# sensorboard.net
KiCad netlist of a schematic drawn in EAGLE
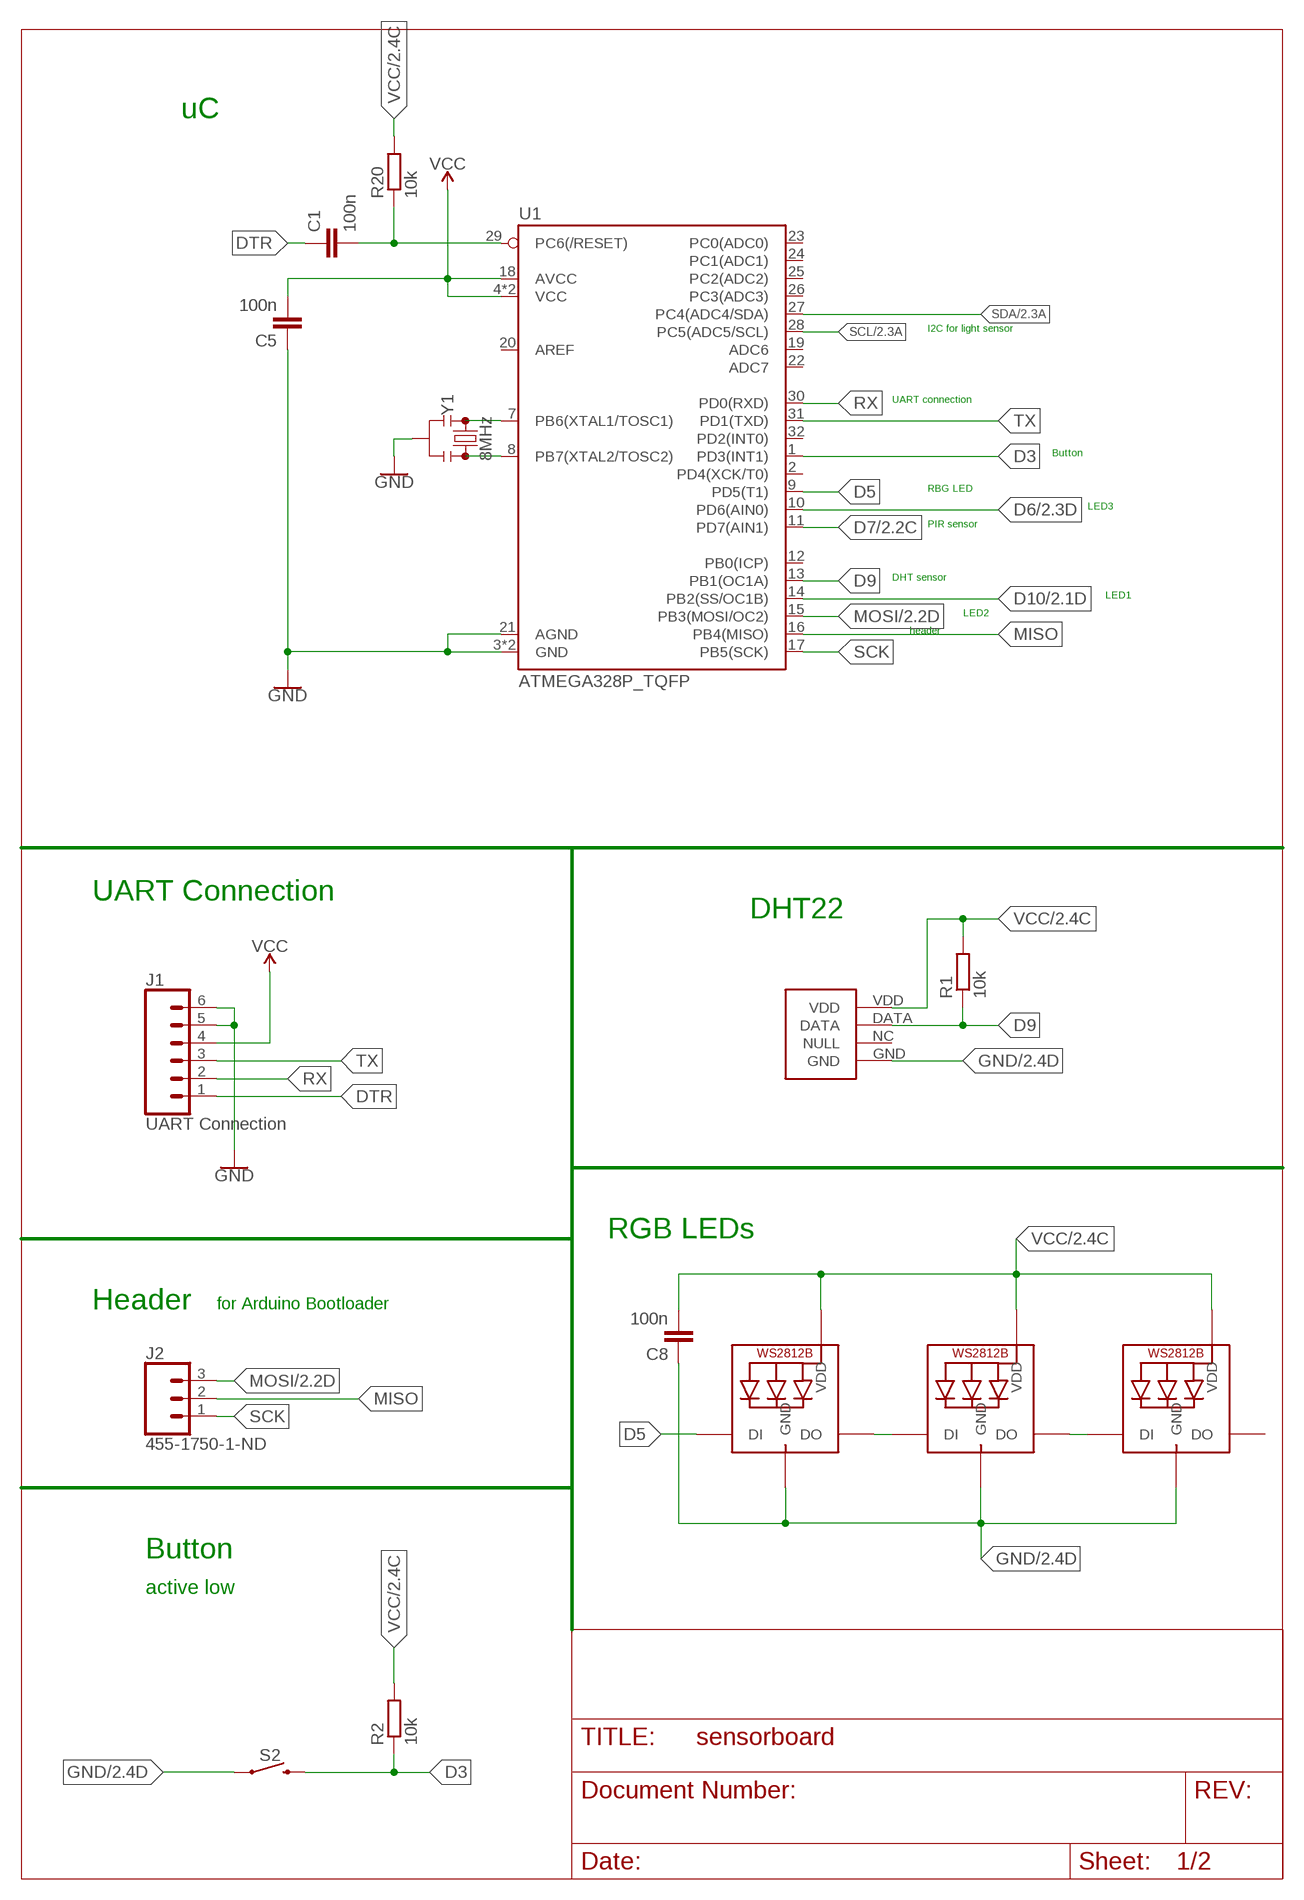
[diagram p0: schematic, sheet 1]
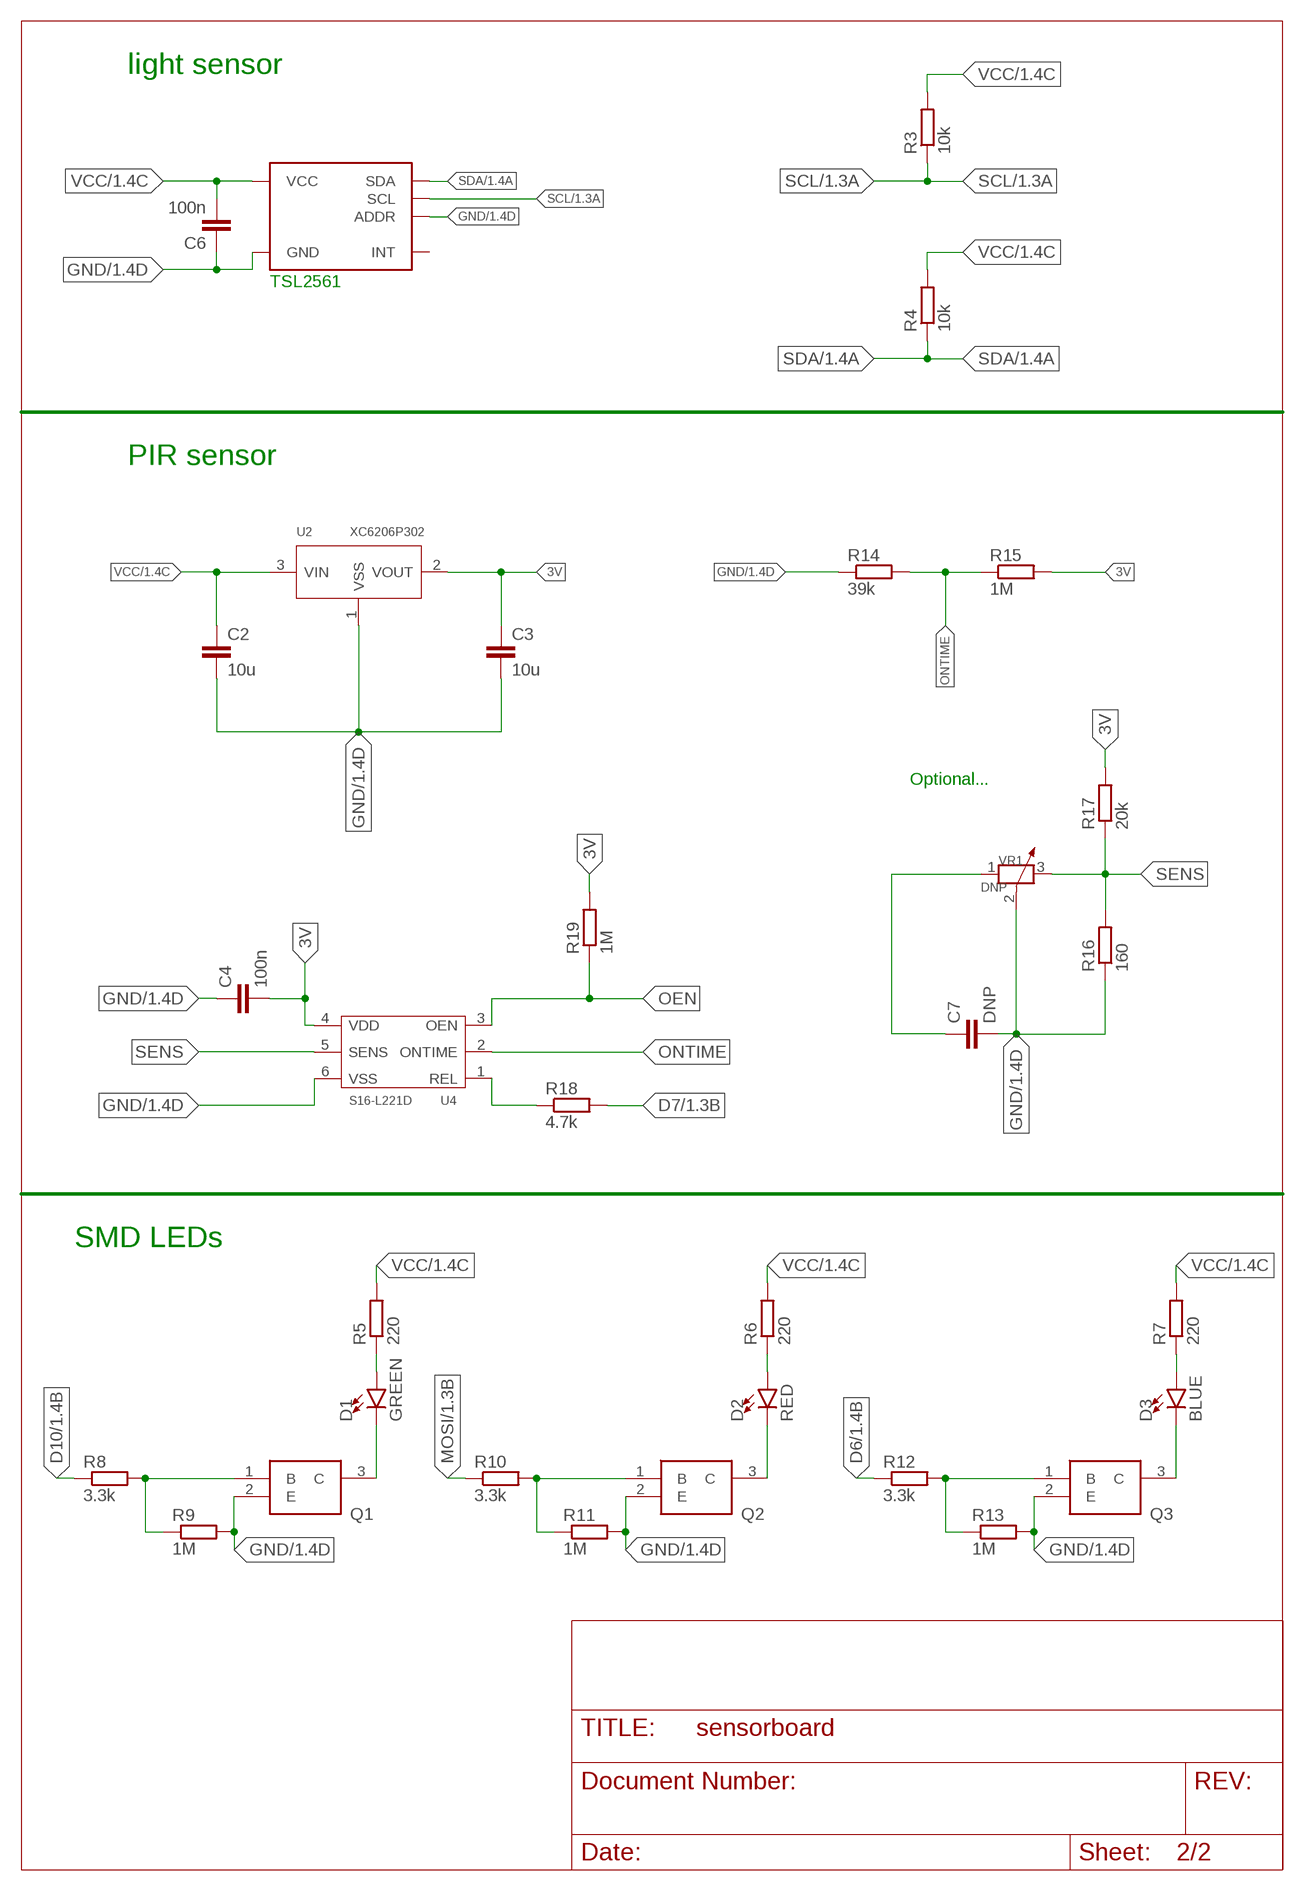
[diagram p1: schematic, sheet 2]

(export (version "E")
  (design (tool "Eeschema 10.0.6"))
  (components
    (comp (ref "C1")
      (value "100n")
      (footprint "eagle-import:C0402")
      (libsource (lib "eagle-import") (part "C-EUC0402"))
    )
    (comp (ref "C5")
      (value "100n")
      (footprint "eagle-import:C0402")
      (libsource (lib "eagle-import") (part "C-EUC0402"))
    )
    (comp (ref "C8")
      (value "100n")
      (footprint "eagle-import:C0402")
      (libsource (lib "eagle-import") (part "C-EUC0402"))
    )
    (comp (ref "DHT22")
      (value "DHT22")
      (footprint "eagle-import:DHT22")
      (libsource (lib "eagle-import") (part "DHT22"))
    )
    (comp (ref "J1")
      (value "UART Connection")
      (footprint "eagle-import:1X06")
      (libsource (lib "eagle-import") (part "CONN_06SILK_FEMALE_PTH"))
    )
    (comp (ref "J2")
      (value "455-1750-1-ND")
      (footprint "eagle-import:1X03")
      (libsource (lib "eagle-import") (part "CONN_03"))
    )
    (comp (ref "LED1")
      (value "WS2812B5050")
      (footprint "eagle-import:WS2812B")
      (fields (field (name "MF") "Seeed Technology") (field (name "MP") "WS2812B"))
      (libsource (lib "eagle-import") (part "WS2812B5050"))
    )
    (comp (ref "LED2")
      (value "WS2812B5050")
      (footprint "eagle-import:WS2812B")
      (fields (field (name "MF") "Seeed Technology") (field (name "MP") "WS2812B"))
      (libsource (lib "eagle-import") (part "WS2812B5050"))
    )
    (comp (ref "LED3")
      (value "WS2812B5050")
      (footprint "eagle-import:WS2812B")
      (fields (field (name "MF") "Seeed Technology") (field (name "MP") "WS2812B"))
      (libsource (lib "eagle-import") (part "WS2812B5050"))
    )
    (comp (ref "R1")
      (value "10k")
      (footprint "eagle-import:R0402")
      (libsource (lib "eagle-import") (part "R-EU_R0402"))
    )
    (comp (ref "R2")
      (value "10k")
      (footprint "eagle-import:R0402")
      (libsource (lib "eagle-import") (part "R-EU_R0402"))
    )
    (comp (ref "R20")
      (value "10k")
      (footprint "eagle-import:R0402")
      (libsource (lib "eagle-import") (part "R-EU_R0402"))
    )
    (comp (ref "S2")
      (value "MOMENTARY-SWITCH-SPST-SMD-6.0X3.5MM")
      (footprint "eagle-import:TACTILE_SWITCH_SMD_6.0X3.5MM")
      (libsource (lib "eagle-import") (part "MOMENTARY-SWITCH-SPST-SMD-6.0X3.5MM"))
    )
    (comp (ref "U1")
      (value "ATMEGA328P_TQFP")
      (footprint "eagle-import:TQFP32-08")
      (libsource (lib "eagle-import") (part "ATMEGA328P_TQFP"))
    )
    (comp (ref "Y1")
      (value "8MHz")
      (footprint "eagle-import:RESONATOR-SMD-3.2X1.3")
      (libsource (lib "eagle-import") (part "RESONATOR-8MHZSMD_3.2X1.3"))
    )
    (comp (ref "C2")
      (value "10u")
      (footprint "eagle-import:C0402")
      (libsource (lib "eagle-import") (part "C-EUC0402"))
    )
    (comp (ref "C3")
      (value "10u")
      (footprint "eagle-import:C0402")
      (libsource (lib "eagle-import") (part "C-EUC0402"))
    )
    (comp (ref "C4")
      (value "100n")
      (footprint "eagle-import:C0402")
      (libsource (lib "eagle-import") (part "C-EUC0402"))
    )
    (comp (ref "C6")
      (value "100n")
      (footprint "eagle-import:C0402")
      (libsource (lib "eagle-import") (part "C-EUC0402"))
    )
    (comp (ref "C7")
      (value "DNP")
      (footprint "eagle-import:C0402")
      (libsource (lib "eagle-import") (part "C-EUC0402"))
    )
    (comp (ref "D1")
      (value "GREEN")
      (footprint "eagle-import:LED-0603")
      (libsource (lib "eagle-import") (part "LED-GREEN0603"))
    )
    (comp (ref "D2")
      (value "RED")
      (footprint "eagle-import:LED-0603")
      (libsource (lib "eagle-import") (part "LED-RED0603"))
    )
    (comp (ref "D3")
      (value "BLUE")
      (footprint "eagle-import:LED-0603")
      (libsource (lib "eagle-import") (part "LED-BLUE0603"))
    )
    (comp (ref "Q1")
      (value "MMSS8050-L-TP")
      (footprint "eagle-import:SOT96P237X122-3N")
      (fields (field (name "MOUSER_PART_NUMBER") "833-MMSS8050-L-TP"))
      (libsource (lib "eagle-import") (part "MMSS8050-L-TP"))
    )
    (comp (ref "Q2")
      (value "MMSS8050-L-TP")
      (footprint "eagle-import:SOT96P237X122-3N")
      (fields (field (name "MOUSER_PART_NUMBER") "833-MMSS8050-L-TP"))
      (libsource (lib "eagle-import") (part "MMSS8050-L-TP"))
    )
    (comp (ref "Q3")
      (value "MMSS8050-L-TP")
      (footprint "eagle-import:SOT96P237X122-3N")
      (fields (field (name "MOUSER_PART_NUMBER") "833-MMSS8050-L-TP"))
      (libsource (lib "eagle-import") (part "MMSS8050-L-TP"))
    )
    (comp (ref "R3")
      (value "10k")
      (footprint "eagle-import:R0402")
      (libsource (lib "eagle-import") (part "R-EU_R0402"))
    )
    (comp (ref "R4")
      (value "10k")
      (footprint "eagle-import:R0402")
      (libsource (lib "eagle-import") (part "R-EU_R0402"))
    )
    (comp (ref "R5")
      (value "220")
      (footprint "eagle-import:R0402")
      (libsource (lib "eagle-import") (part "R-EU_R0402"))
    )
    (comp (ref "R6")
      (value "220")
      (footprint "eagle-import:R0402")
      (libsource (lib "eagle-import") (part "R-EU_R0402"))
    )
    (comp (ref "R7")
      (value "220")
      (footprint "eagle-import:R0402")
      (libsource (lib "eagle-import") (part "R-EU_R0402"))
    )
    (comp (ref "R8")
      (value "3.3k")
      (footprint "eagle-import:R0402")
      (libsource (lib "eagle-import") (part "R-EU_R0402"))
    )
    (comp (ref "R9")
      (value "1M")
      (footprint "eagle-import:R0402")
      (libsource (lib "eagle-import") (part "R-EU_R0402"))
    )
    (comp (ref "R10")
      (value "3.3k")
      (footprint "eagle-import:R0402")
      (libsource (lib "eagle-import") (part "R-EU_R0402"))
    )
    (comp (ref "R11")
      (value "1M")
      (footprint "eagle-import:R0402")
      (libsource (lib "eagle-import") (part "R-EU_R0402"))
    )
    (comp (ref "R12")
      (value "3.3k")
      (footprint "eagle-import:R0402")
      (libsource (lib "eagle-import") (part "R-EU_R0402"))
    )
    (comp (ref "R13")
      (value "1M")
      (footprint "eagle-import:R0402")
      (libsource (lib "eagle-import") (part "R-EU_R0402"))
    )
    (comp (ref "R14")
      (value "39k")
      (footprint "eagle-import:R0402")
      (libsource (lib "eagle-import") (part "R-EU_R0402"))
    )
    (comp (ref "R15")
      (value "1M")
      (footprint "eagle-import:R0402")
      (libsource (lib "eagle-import") (part "R-EU_R0402"))
    )
    (comp (ref "R16")
      (value "160")
      (footprint "eagle-import:R0402")
      (libsource (lib "eagle-import") (part "R-EU_R0402"))
    )
    (comp (ref "R17")
      (value "20k")
      (footprint "eagle-import:R0402")
      (libsource (lib "eagle-import") (part "R-EU_R0402"))
    )
    (comp (ref "R18")
      (value "4.7k")
      (footprint "eagle-import:R0402")
      (libsource (lib "eagle-import") (part "R-EU_R0402"))
    )
    (comp (ref "R19")
      (value "1M")
      (footprint "eagle-import:R0402")
      (libsource (lib "eagle-import") (part "R-EU_R0402"))
    )
    (comp (ref "TSL2561")
      (value "TSL2561FN")
      (footprint "eagle-import:DFN-6")
      (fields (field (name "MF") "ams") (field (name "MP") "TSL2561"))
      (libsource (lib "eagle-import") (part "TSL2561FN"))
    )
    (comp (ref "U2")
      (value "XC6206P302")
      (footprint "eagle-import:SOT-23")
      (libsource (lib "eagle-import") (part "PMIC-XC6206PMR"))
    )
    (comp (ref "U4")
      (value "S16-L221D")
      (footprint "eagle-import:6P-SMD-6X6MM")
      (libsource (lib "eagle-import") (part "S16-L221D"))
    )
    (comp (ref "VR1")
      (value "DNP")
      (footprint "eagle-import:ADJR3-SMD-4.6X3.7MM")
      (libsource (lib "eagle-import") (part "RES-ADJ'RTRIM3214W'"))
    )
  )
  (nets
    (net (code "1") (name "3V") (class "Default")
      (node (ref "C3") (pin "1") (pinfunction "1_1") (pintype "passive"))
      (node (ref "C4") (pin "2") (pinfunction "2_2") (pintype "passive"))
      (node (ref "R15") (pin "2") (pinfunction "2_2") (pintype "passive"))
      (node (ref "R17") (pin "2") (pinfunction "2_2") (pintype "passive"))
      (node (ref "R19") (pin "2") (pinfunction "2_2") (pintype "passive"))
      (node (ref "U2") (pin "2") (pinfunction "VOUT_2") (pintype "bidirectional"))
      (node (ref "U4") (pin "4") (pinfunction "VDD_4") (pintype "bidirectional"))
    )
    (net (code "2") (name "D3") (class "Default")
      (node (ref "R2") (pin "1") (pinfunction "1_1") (pintype "passive"))
      (node (ref "S2") (pin "2") (pinfunction "2_2") (pintype "passive"))
      (node (ref "U1") (pin "1") (pinfunction "PD3(INT1)_1") (pintype "bidirectional"))
    )
    (net (code "3") (name "D5") (class "Default")
      (node (ref "LED2") (pin "4-DIN") (pinfunction "DI_4-DIN") (pintype "input"))
      (node (ref "U1") (pin "9") (pinfunction "PD5(T1)_9") (pintype "bidirectional"))
    )
    (net (code "4") (name "D6") (class "Default")
      (node (ref "R12") (pin "1") (pinfunction "1_1") (pintype "passive"))
      (node (ref "U1") (pin "10") (pinfunction "PD6(AIN0)_10") (pintype "bidirectional"))
    )
    (net (code "5") (name "D7") (class "Default")
      (node (ref "R18") (pin "2") (pinfunction "2_2") (pintype "passive"))
      (node (ref "U1") (pin "11") (pinfunction "PD7(AIN1)_11") (pintype "bidirectional"))
    )
    (net (code "6") (name "D9") (class "Default")
      (node (ref "DHT22") (pin "DATA") (pinfunction "DATA_DATA") (pintype "output"))
      (node (ref "R1") (pin "1") (pinfunction "1_1") (pintype "passive"))
      (node (ref "U1") (pin "13") (pinfunction "PB1(OC1A)_13") (pintype "bidirectional"))
    )
    (net (code "7") (name "D10") (class "Default")
      (node (ref "R8") (pin "1") (pinfunction "1_1") (pintype "passive"))
      (node (ref "U1") (pin "14") (pinfunction "PB2(SS/OC1B)_14") (pintype "bidirectional"))
    )
    (net (code "8") (name "DTR") (class "Default")
      (node (ref "C1") (pin "1") (pinfunction "1_1") (pintype "passive"))
      (node (ref "J1") (pin "1") (pinfunction "1_1") (pintype "passive"))
    )
    (net (code "9") (name "GND") (class "Default")
      (node (ref "C2") (pin "2") (pinfunction "2_2") (pintype "passive"))
      (node (ref "C3") (pin "2") (pinfunction "2_2") (pintype "passive"))
      (node (ref "C4") (pin "1") (pinfunction "1_1") (pintype "passive"))
      (node (ref "C5") (pin "1") (pinfunction "1_1") (pintype "passive"))
      (node (ref "C6") (pin "1") (pinfunction "1_1") (pintype "passive"))
      (node (ref "C7") (pin "2") (pinfunction "2_2") (pintype "passive"))
      (node (ref "C8") (pin "1") (pinfunction "1_1") (pintype "passive"))
      (node (ref "DHT22") (pin "GND") (pinfunction "GND_GND") (pintype "power_in"))
      (node (ref "J1") (pin "5") (pinfunction "5_5") (pintype "passive"))
      (node (ref "J1") (pin "6") (pinfunction "6_6") (pintype "passive"))
      (node (ref "LED1") (pin "3-GND") (pinfunction "GND_3-GND") (pintype "power_in"))
      (node (ref "LED2") (pin "3-GND") (pinfunction "GND_3-GND") (pintype "power_in"))
      (node (ref "LED3") (pin "3-GND") (pinfunction "GND_3-GND") (pintype "power_in"))
      (node (ref "Q1") (pin "2") (pinfunction "E_2") (pintype "bidirectional"))
      (node (ref "Q2") (pin "2") (pinfunction "E_2") (pintype "bidirectional"))
      (node (ref "Q3") (pin "2") (pinfunction "E_2") (pintype "bidirectional"))
      (node (ref "R11") (pin "2") (pinfunction "2_2") (pintype "passive"))
      (node (ref "R13") (pin "2") (pinfunction "2_2") (pintype "passive"))
      (node (ref "R14") (pin "1") (pinfunction "1_1") (pintype "passive"))
      (node (ref "R16") (pin "1") (pinfunction "1_1") (pintype "passive"))
      (node (ref "R9") (pin "2") (pinfunction "2_2") (pintype "passive"))
      (node (ref "S2") (pin "1") (pinfunction "1_1") (pintype "passive"))
      (node (ref "TSL2561") (pin "ADDR") (pinfunction "ADDR_ADDR") (pintype "bidirectional"))
      (node (ref "TSL2561") (pin "GND") (pinfunction "GND_GND") (pintype "bidirectional"))
      (node (ref "U1") (pin "21") (pinfunction "AGND_21") (pintype "bidirectional"))
      (node (ref "U1") (pin "3") (pinfunction "GND_3") (pintype "bidirectional"))
      (node (ref "U1") (pin "5") (pinfunction "GND_5") (pintype "bidirectional"))
      (node (ref "U2") (pin "1") (pinfunction "VSS_1") (pintype "bidirectional"))
      (node (ref "U4") (pin "6") (pinfunction "VSS_6") (pintype "bidirectional"))
      (node (ref "VR1") (pin "2") (pinfunction "3_2") (pintype "passive"))
      (node (ref "Y1") (pin "2") (pinfunction "2_2") (pintype "passive"))
    )
    (net (code "10") (name "MISO") (class "Default")
      (node (ref "J2") (pin "2") (pinfunction "2_2") (pintype "passive"))
      (node (ref "U1") (pin "16") (pinfunction "PB4(MISO)_16") (pintype "bidirectional"))
    )
    (net (code "11") (name "MOSI") (class "Default")
      (node (ref "J2") (pin "3") (pinfunction "3_3") (pintype "passive"))
      (node (ref "R10") (pin "1") (pinfunction "1_1") (pintype "passive"))
      (node (ref "U1") (pin "15") (pinfunction "PB3(MOSI/OC2)_15") (pintype "bidirectional"))
    )
    (net (code "12") (name "Net-(C7-Pad1)") (class "Default")
      (node (ref "C7") (pin "1") (pinfunction "1_1") (pintype "passive"))
      (node (ref "VR1") (pin "1") (pinfunction "1_1") (pintype "passive"))
    )
    (net (code "13") (name "Net-(D1-PadA)") (class "Default")
      (node (ref "D1") (pin "A") (pinfunction "A_A") (pintype "passive"))
      (node (ref "R5") (pin "1") (pinfunction "1_1") (pintype "passive"))
    )
    (net (code "14") (name "Net-(D2-PadA)") (class "Default")
      (node (ref "D2") (pin "A") (pinfunction "A_A") (pintype "passive"))
      (node (ref "R6") (pin "1") (pinfunction "1_1") (pintype "passive"))
    )
    (net (code "15") (name "Net-(D3-PadA)") (class "Default")
      (node (ref "D3") (pin "A") (pinfunction "A_A") (pintype "passive"))
      (node (ref "R7") (pin "1") (pinfunction "1_1") (pintype "passive"))
    )
    (net (code "16") (name "Net-(LED1-DI)") (class "Default")
      (node (ref "LED1") (pin "4-DIN") (pinfunction "DI_4-DIN") (pintype "input"))
      (node (ref "LED2") (pin "2-DOUT") (pinfunction "DO_2-DOUT") (pintype "output"))
    )
    (net (code "17") (name "Net-(LED1-DO)") (class "Default")
      (node (ref "LED1") (pin "2-DOUT") (pinfunction "DO_2-DOUT") (pintype "output"))
      (node (ref "LED3") (pin "4-DIN") (pinfunction "DI_4-DIN") (pintype "input"))
    )
    (net (code "18") (name "Net-(Q1-B)") (class "Default")
      (node (ref "Q1") (pin "1") (pinfunction "B_1") (pintype "bidirectional"))
      (node (ref "R8") (pin "2") (pinfunction "2_2") (pintype "passive"))
      (node (ref "R9") (pin "1") (pinfunction "1_1") (pintype "passive"))
    )
    (net (code "19") (name "Net-(Q1-C)") (class "Default")
      (node (ref "D1") (pin "C") (pinfunction "C_C") (pintype "passive"))
      (node (ref "Q1") (pin "3") (pinfunction "C_3") (pintype "bidirectional"))
    )
    (net (code "20") (name "Net-(Q2-B)") (class "Default")
      (node (ref "Q2") (pin "1") (pinfunction "B_1") (pintype "bidirectional"))
      (node (ref "R10") (pin "2") (pinfunction "2_2") (pintype "passive"))
      (node (ref "R11") (pin "1") (pinfunction "1_1") (pintype "passive"))
    )
    (net (code "21") (name "Net-(Q2-C)") (class "Default")
      (node (ref "D2") (pin "C") (pinfunction "C_C") (pintype "passive"))
      (node (ref "Q2") (pin "3") (pinfunction "C_3") (pintype "bidirectional"))
    )
    (net (code "22") (name "Net-(Q3-B)") (class "Default")
      (node (ref "Q3") (pin "1") (pinfunction "B_1") (pintype "bidirectional"))
      (node (ref "R12") (pin "2") (pinfunction "2_2") (pintype "passive"))
      (node (ref "R13") (pin "1") (pinfunction "1_1") (pintype "passive"))
    )
    (net (code "23") (name "Net-(Q3-C)") (class "Default")
      (node (ref "D3") (pin "C") (pinfunction "C_C") (pintype "passive"))
      (node (ref "Q3") (pin "3") (pinfunction "C_3") (pintype "bidirectional"))
    )
    (net (code "24") (name "Net-(U1-PB6(XTAL1{slash}TOSC1))") (class "Default")
      (node (ref "U1") (pin "7") (pinfunction "PB6(XTAL1/TOSC1)_7") (pintype "bidirectional"))
      (node (ref "Y1") (pin "1") (pinfunction "1_1") (pintype "passive"))
    )
    (net (code "25") (name "Net-(U1-PB7(XTAL2{slash}TOSC2))") (class "Default")
      (node (ref "U1") (pin "8") (pinfunction "PB7(XTAL2/TOSC2)_8") (pintype "bidirectional"))
      (node (ref "Y1") (pin "3") (pinfunction "3_3") (pintype "passive"))
    )
    (net (code "26") (name "Net-(U1-PC6({slash}RESET))") (class "Default")
      (node (ref "C1") (pin "2") (pinfunction "2_2") (pintype "passive"))
      (node (ref "R20") (pin "1") (pinfunction "1_1") (pintype "passive"))
      (node (ref "U1") (pin "29") (pinfunction "PC6(/RESET)_29") (pintype "bidirectional"))
    )
    (net (code "27") (name "Net-(U4-REL)") (class "Default")
      (node (ref "R18") (pin "1") (pinfunction "1_1") (pintype "passive"))
      (node (ref "U4") (pin "1") (pinfunction "REL_1") (pintype "bidirectional"))
    )
    (net (code "28") (name "OEN") (class "Default")
      (node (ref "R19") (pin "1") (pinfunction "1_1") (pintype "passive"))
      (node (ref "U4") (pin "3") (pinfunction "OEN_3") (pintype "bidirectional"))
    )
    (net (code "29") (name "ONTIME") (class "Default")
      (node (ref "R14") (pin "2") (pinfunction "2_2") (pintype "passive"))
      (node (ref "R15") (pin "1") (pinfunction "1_1") (pintype "passive"))
      (node (ref "U4") (pin "2") (pinfunction "ONTIME_2") (pintype "bidirectional"))
    )
    (net (code "30") (name "RX") (class "Default")
      (node (ref "J1") (pin "2") (pinfunction "2_2") (pintype "passive"))
      (node (ref "U1") (pin "30") (pinfunction "PD0(RXD)_30") (pintype "bidirectional"))
    )
    (net (code "31") (name "SCK") (class "Default")
      (node (ref "J2") (pin "1") (pinfunction "1_1") (pintype "passive"))
      (node (ref "U1") (pin "17") (pinfunction "PB5(SCK)_17") (pintype "bidirectional"))
    )
    (net (code "32") (name "SCL") (class "Default")
      (node (ref "R3") (pin "1") (pinfunction "1_1") (pintype "passive"))
      (node (ref "TSL2561") (pin "SCL") (pinfunction "SCL_SCL") (pintype "bidirectional"))
      (node (ref "U1") (pin "28") (pinfunction "PC5(ADC5/SCL)_28") (pintype "bidirectional"))
    )
    (net (code "33") (name "SDA") (class "Default")
      (node (ref "R4") (pin "1") (pinfunction "1_1") (pintype "passive"))
      (node (ref "TSL2561") (pin "SDA") (pinfunction "SDA_SDA") (pintype "bidirectional"))
      (node (ref "U1") (pin "27") (pinfunction "PC4(ADC4/SDA)_27") (pintype "bidirectional"))
    )
    (net (code "34") (name "SENS") (class "Default")
      (node (ref "R16") (pin "2") (pinfunction "2_2") (pintype "passive"))
      (node (ref "R17") (pin "1") (pinfunction "1_1") (pintype "passive"))
      (node (ref "U4") (pin "5") (pinfunction "SENS_5") (pintype "bidirectional"))
      (node (ref "VR1") (pin "3") (pinfunction "2_3") (pintype "passive"))
    )
    (net (code "35") (name "TX") (class "Default")
      (node (ref "J1") (pin "3") (pinfunction "3_3") (pintype "passive"))
      (node (ref "U1") (pin "31") (pinfunction "PD1(TXD)_31") (pintype "bidirectional"))
    )
    (net (code "36") (name "VCC") (class "Default")
      (node (ref "C2") (pin "1") (pinfunction "1_1") (pintype "passive"))
      (node (ref "C5") (pin "2") (pinfunction "2_2") (pintype "passive"))
      (node (ref "C6") (pin "2") (pinfunction "2_2") (pintype "passive"))
      (node (ref "C8") (pin "2") (pinfunction "2_2") (pintype "passive"))
      (node (ref "DHT22") (pin "VDD") (pinfunction "VDD_VDD") (pintype "power_in"))
      (node (ref "J1") (pin "4") (pinfunction "4_4") (pintype "passive"))
      (node (ref "LED1") (pin "1-VDD") (pinfunction "VDD_1-VDD") (pintype "power_in"))
      (node (ref "LED2") (pin "1-VDD") (pinfunction "VDD_1-VDD") (pintype "power_in"))
      (node (ref "LED3") (pin "1-VDD") (pinfunction "VDD_1-VDD") (pintype "power_in"))
      (node (ref "R1") (pin "2") (pinfunction "2_2") (pintype "passive"))
      (node (ref "R2") (pin "2") (pinfunction "2_2") (pintype "passive"))
      (node (ref "R20") (pin "2") (pinfunction "2_2") (pintype "passive"))
      (node (ref "R3") (pin "2") (pinfunction "2_2") (pintype "passive"))
      (node (ref "R4") (pin "2") (pinfunction "2_2") (pintype "passive"))
      (node (ref "R5") (pin "2") (pinfunction "2_2") (pintype "passive"))
      (node (ref "R6") (pin "2") (pinfunction "2_2") (pintype "passive"))
      (node (ref "R7") (pin "2") (pinfunction "2_2") (pintype "passive"))
      (node (ref "TSL2561") (pin "VDD") (pinfunction "VCC_VDD") (pintype "bidirectional"))
      (node (ref "U1") (pin "18") (pinfunction "AVCC_18") (pintype "bidirectional"))
      (node (ref "U1") (pin "4") (pinfunction "VCC_4") (pintype "bidirectional"))
      (node (ref "U1") (pin "6") (pinfunction "VCC_6") (pintype "bidirectional"))
      (node (ref "U2") (pin "3") (pinfunction "VIN_3") (pintype "bidirectional"))
    )
    (net (code "37") (name "unconnected-(DHT22-NULL-PadNC)") (class "Default")
      (node (ref "DHT22") (pin "NC") (pinfunction "NULL_NC") (pintype "no_connect"))
    )
    (net (code "38") (name "unconnected-(LED3-DO-Pad2-DOUT)") (class "Default")
      (node (ref "LED3") (pin "2-DOUT") (pinfunction "DO_2-DOUT") (pintype "output"))
    )
    (net (code "39") (name "unconnected-(TSL2561-PadINT)") (class "Default")
      (node (ref "TSL2561") (pin "INT") (pinfunction "INT_INT") (pintype "bidirectional"))
    )
    (net (code "40") (name "unconnected-(U1-ADC6-Pad19)") (class "Default")
      (node (ref "U1") (pin "19") (pinfunction "ADC6_19") (pintype "bidirectional"))
    )
    (net (code "41") (name "unconnected-(U1-ADC7-Pad22)") (class "Default")
      (node (ref "U1") (pin "22") (pinfunction "ADC7_22") (pintype "bidirectional"))
    )
    (net (code "42") (name "unconnected-(U1-AREF-Pad20)") (class "Default")
      (node (ref "U1") (pin "20") (pinfunction "AREF_20") (pintype "bidirectional"))
    )
    (net (code "43") (name "unconnected-(U1-PB0(ICP)-Pad12)") (class "Default")
      (node (ref "U1") (pin "12") (pinfunction "PB0(ICP)_12") (pintype "bidirectional"))
    )
    (net (code "44") (name "unconnected-(U1-PC0(ADC0)-Pad23)") (class "Default")
      (node (ref "U1") (pin "23") (pinfunction "PC0(ADC0)_23") (pintype "bidirectional"))
    )
    (net (code "45") (name "unconnected-(U1-PC1(ADC1)-Pad24)") (class "Default")
      (node (ref "U1") (pin "24") (pinfunction "PC1(ADC1)_24") (pintype "bidirectional"))
    )
    (net (code "46") (name "unconnected-(U1-PC2(ADC2)-Pad25)") (class "Default")
      (node (ref "U1") (pin "25") (pinfunction "PC2(ADC2)_25") (pintype "bidirectional"))
    )
    (net (code "47") (name "unconnected-(U1-PC3(ADC3)-Pad26)") (class "Default")
      (node (ref "U1") (pin "26") (pinfunction "PC3(ADC3)_26") (pintype "bidirectional"))
    )
    (net (code "48") (name "unconnected-(U1-PD2(INT0)-Pad32)") (class "Default")
      (node (ref "U1") (pin "32") (pinfunction "PD2(INT0)_32") (pintype "bidirectional"))
    )
    (net (code "49") (name "unconnected-(U1-PD4(XCK{slash}T0)-Pad2)") (class "Default")
      (node (ref "U1") (pin "2") (pinfunction "PD4(XCK/T0)_2") (pintype "bidirectional"))
    )
  )
)
